# cd4017_ir_remote.net
KiCad netlist of a schematic drawn in EAGLE
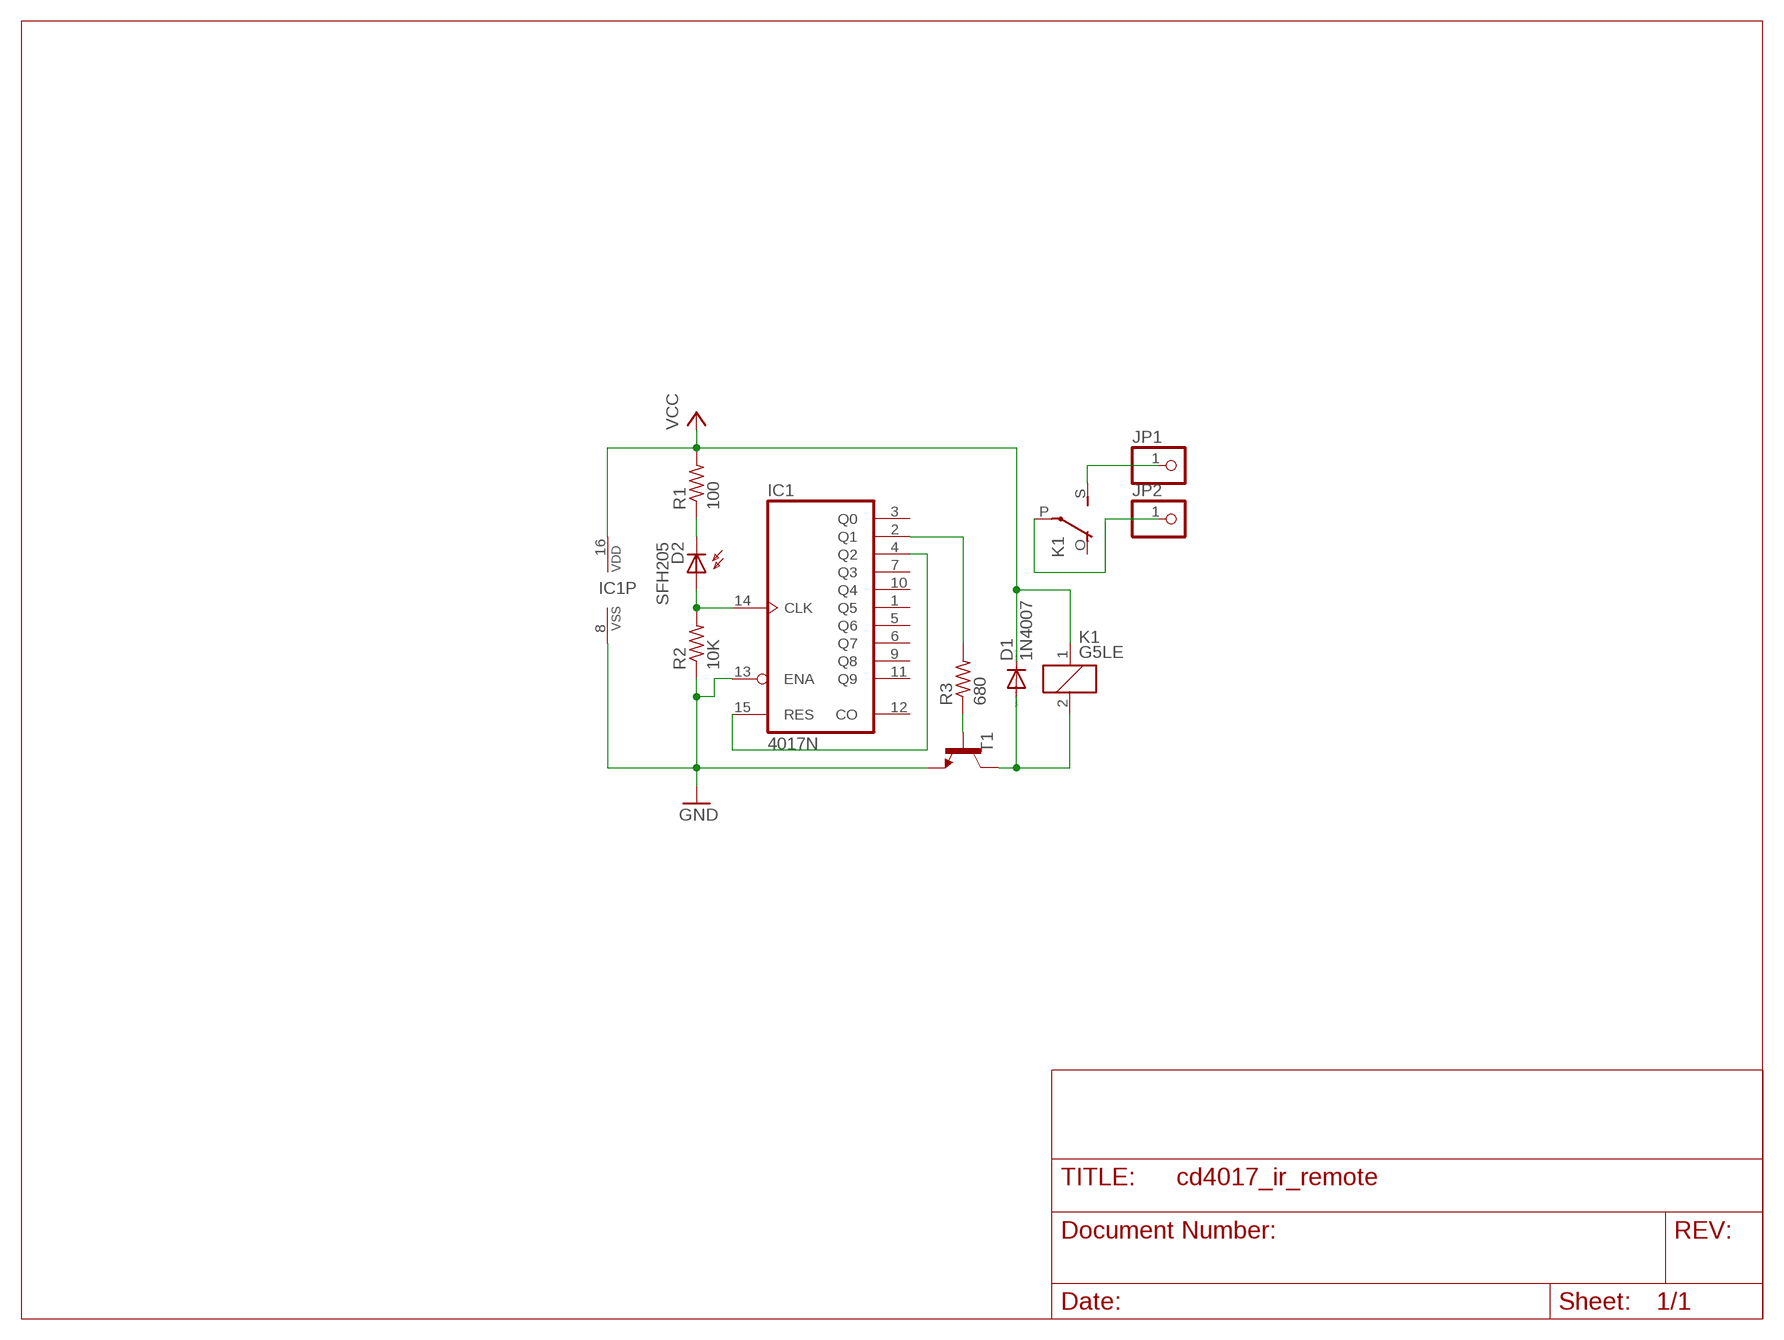
[diagram p0: schematic, sheet 1]

(export (version "E")
  (design (tool "Eeschema 10.0.6"))
  (components
    (comp (ref "D1")
      (value "1N4007")
      (footprint "eagle-import:DO41-10")
      (libsource (lib "eagle-import") (part "1N4004"))
    )
    (comp (ref "D2")
      (value "SFH205")
      (footprint "eagle-import:SFH205")
      (libsource (lib "eagle-import") (part "SFH205"))
    )
    (comp (ref "IC1")
      (value "4017N")
      (footprint "eagle-import:DIL16")
      (libsource (lib "eagle-import") (part "4017N"))
    )
    (comp (ref "JP1")
      (value "PINHD-1X1")
      (footprint "eagle-import:1X01")
      (libsource (lib "eagle-import") (part "PINHD-1X1"))
    )
    (comp (ref "JP2")
      (value "PINHD-1X1")
      (footprint "eagle-import:1X01")
      (libsource (lib "eagle-import") (part "PINHD-1X1"))
    )
    (comp (ref "K1")
      (value "G5LE")
      (footprint "eagle-import:G5LE")
      (libsource (lib "eagle-import") (part "G5LE"))
    )
    (comp (ref "R1")
      (value "100")
      (footprint "eagle-import:0204_7")
      (libsource (lib "eagle-import") (part "R-US_0204/7"))
    )
    (comp (ref "R2")
      (value "10K")
      (footprint "eagle-import:0204_7")
      (libsource (lib "eagle-import") (part "R-US_0204/7"))
    )
    (comp (ref "R3")
      (value "680")
      (footprint "eagle-import:0204_7")
      (libsource (lib "eagle-import") (part "R-US_0204/7"))
    )
    (comp (ref "T1")
      (value "2N2222-NPN-TO92-EBC")
      (footprint "eagle-import:TO92-EBC")
      (libsource (lib "eagle-import") (part "-NPN-TO92-EBC2N2222"))
    )
  )
  (nets
    (net (code "1") (name "GND") (class "Default")
      (node (ref "IC1") (pin "13") (pinfunction "ENA_13") (pintype "input"))
      (node (ref "IC1") (pin "8") (pinfunction "VSS_8") (pintype "power_in"))
      (node (ref "R2") (pin "1") (pinfunction "1_1") (pintype "passive"))
      (node (ref "T1") (pin "E") (pinfunction "E_E") (pintype "passive"))
    )
    (net (code "2") (name "Net-(D1-PadA)") (class "Default")
      (node (ref "D1") (pin "A") (pinfunction "A_A") (pintype "passive"))
      (node (ref "K1") (pin "2") (pinfunction "2_2") (pintype "passive"))
      (node (ref "T1") (pin "C") (pinfunction "C_C") (pintype "passive"))
    )
    (net (code "3") (name "Net-(D2-C)") (class "Default")
      (node (ref "D2") (pin "K") (pinfunction "C_K") (pintype "passive"))
      (node (ref "R1") (pin "1") (pinfunction "1_1") (pintype "passive"))
    )
    (net (code "4") (name "Net-(IC1A-CLK)") (class "Default")
      (node (ref "D2") (pin "A") (pinfunction "A_A") (pintype "passive"))
      (node (ref "IC1") (pin "14") (pinfunction "CLK_14") (pintype "input"))
      (node (ref "R2") (pin "2") (pinfunction "2_2") (pintype "passive"))
    )
    (net (code "5") (name "Net-(IC1A-Q1)") (class "Default")
      (node (ref "IC1") (pin "2") (pinfunction "Q1_2") (pintype "output"))
      (node (ref "R3") (pin "2") (pinfunction "2_2") (pintype "passive"))
    )
    (net (code "6") (name "Net-(IC1A-Q2)") (class "Default")
      (node (ref "IC1") (pin "15") (pinfunction "RES_15") (pintype "input"))
      (node (ref "IC1") (pin "4") (pinfunction "Q2_4") (pintype "output"))
    )
    (net (code "7") (name "Net-(JP1-Pad1)") (class "Default")
      (node (ref "JP1") (pin "1") (pinfunction "1_1") (pintype "passive"))
      (node (ref "K1") (pin "S") (pinfunction "S_S") (pintype "passive"))
    )
    (net (code "8") (name "Net-(JP2-Pad1)") (class "Default")
      (node (ref "JP2") (pin "1") (pinfunction "1_1") (pintype "passive"))
      (node (ref "K1") (pin "P") (pinfunction "P_P") (pintype "passive"))
    )
    (net (code "9") (name "Net-(R3-Pad1)") (class "Default")
      (node (ref "R3") (pin "1") (pinfunction "1_1") (pintype "passive"))
      (node (ref "T1") (pin "B") (pinfunction "B_B") (pintype "passive"))
    )
    (net (code "10") (name "VCC") (class "Default")
      (node (ref "D1") (pin "C") (pinfunction "C_C") (pintype "passive"))
      (node (ref "IC1") (pin "16") (pinfunction "VDD_16") (pintype "power_in"))
      (node (ref "K1") (pin "1") (pinfunction "1_1") (pintype "passive"))
      (node (ref "R1") (pin "2") (pinfunction "2_2") (pintype "passive"))
    )
    (net (code "11") (name "unconnected-(IC1A-CO-Pad12)") (class "Default")
      (node (ref "IC1") (pin "12") (pinfunction "CO_12") (pintype "output"))
    )
    (net (code "12") (name "unconnected-(IC1A-Q0-Pad3)") (class "Default")
      (node (ref "IC1") (pin "3") (pinfunction "Q0_3") (pintype "output"))
    )
    (net (code "13") (name "unconnected-(IC1A-Q3-Pad7)") (class "Default")
      (node (ref "IC1") (pin "7") (pinfunction "Q3_7") (pintype "output"))
    )
    (net (code "14") (name "unconnected-(IC1A-Q4-Pad10)") (class "Default")
      (node (ref "IC1") (pin "10") (pinfunction "Q4_10") (pintype "output"))
    )
    (net (code "15") (name "unconnected-(IC1A-Q5-Pad1)") (class "Default")
      (node (ref "IC1") (pin "1") (pinfunction "Q5_1") (pintype "output"))
    )
    (net (code "16") (name "unconnected-(IC1A-Q6-Pad5)") (class "Default")
      (node (ref "IC1") (pin "5") (pinfunction "Q6_5") (pintype "output"))
    )
    (net (code "17") (name "unconnected-(IC1A-Q7-Pad6)") (class "Default")
      (node (ref "IC1") (pin "6") (pinfunction "Q7_6") (pintype "output"))
    )
    (net (code "18") (name "unconnected-(IC1A-Q8-Pad9)") (class "Default")
      (node (ref "IC1") (pin "9") (pinfunction "Q8_9") (pintype "output"))
    )
    (net (code "19") (name "unconnected-(IC1A-Q9-Pad11)") (class "Default")
      (node (ref "IC1") (pin "11") (pinfunction "Q9_11") (pintype "output"))
    )
    (net (code "20") (name "unconnected-(K1-PadO)") (class "Default")
      (node (ref "K1") (pin "O") (pinfunction "O_O") (pintype "passive"))
    )
  )
)
